# 8Bit-audio-7524-axelb.net
KiCad netlist of a schematic drawn in EAGLE
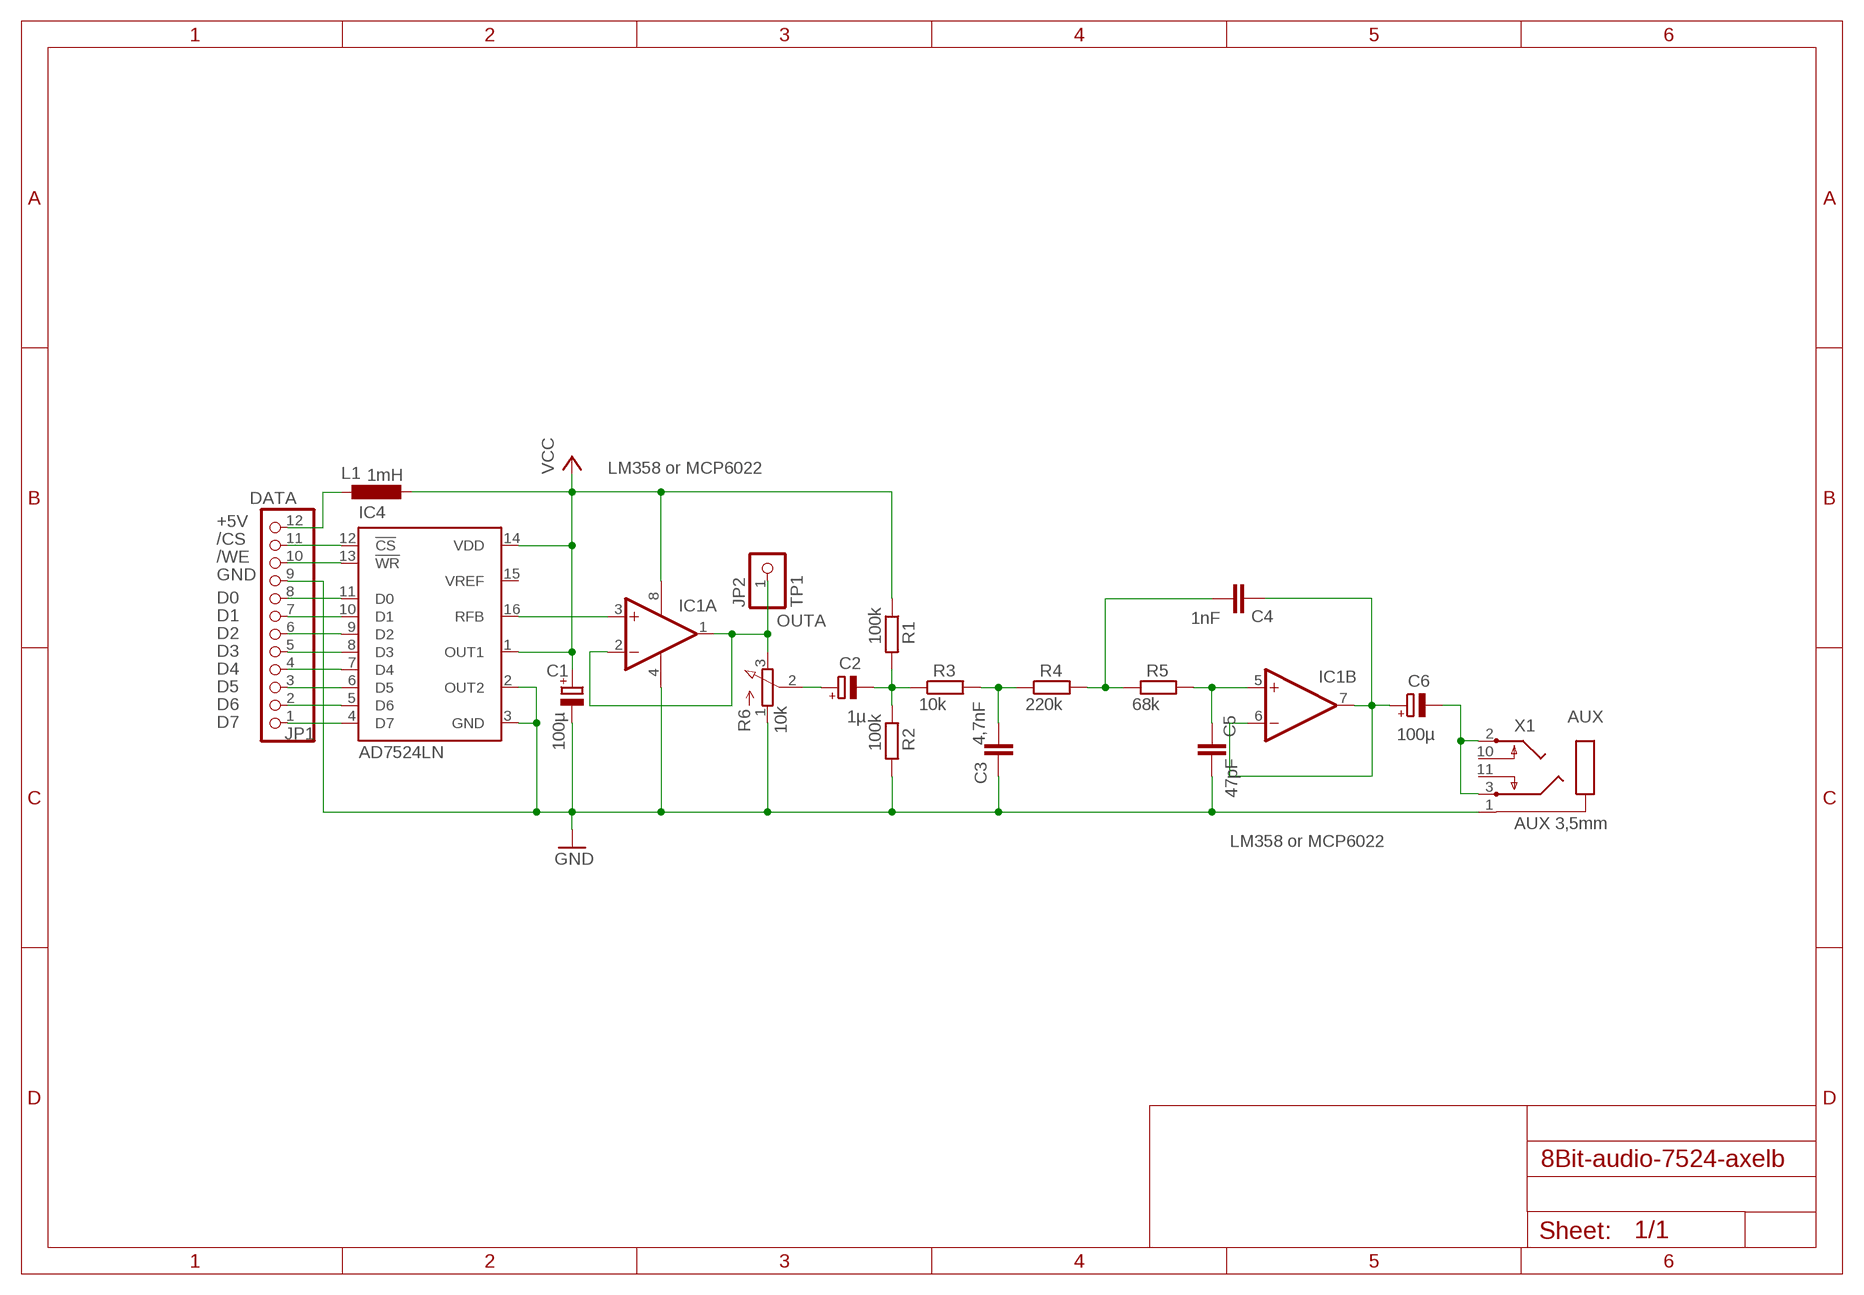
[diagram p0: schematic, sheet 1]

(export (version "E")
  (design (tool "Eeschema 10.0.6"))
  (components
    (comp (ref "C1")
      (value "100µ")
      (footprint "eagle-import:E5-5")
      (libsource (lib "eagle-import") (part "CPOL-EUE5-5"))
    )
    (comp (ref "C2")
      (value "1µ")
      (footprint "eagle-import:E5-5")
      (libsource (lib "eagle-import") (part "CPOL-EUE5-5"))
    )
    (comp (ref "C3")
      (value "4,7nF")
      (footprint "eagle-import:C075-032X103")
      (libsource (lib "eagle-import") (part "C-EU075-032X103"))
    )
    (comp (ref "C4")
      (value "1nF")
      (footprint "eagle-import:C075-032X103")
      (libsource (lib "eagle-import") (part "C-EU075-032X103"))
    )
    (comp (ref "C5")
      (value "47pF")
      (footprint "eagle-import:C075-032X103")
      (libsource (lib "eagle-import") (part "C-EU075-032X103"))
    )
    (comp (ref "C6")
      (value "100µ")
      (footprint "eagle-import:E5-5")
      (libsource (lib "eagle-import") (part "CPOL-EUE5-5"))
    )
    (comp (ref "IC1")
      (value "LM358 or MCP6022")
      (footprint "eagle-import:DIL08")
      (libsource (lib "eagle-import") (part "LM358N"))
    )
    (comp (ref "IC4")
      (value "AD7524LN")
      (footprint "eagle-import:DIL16")
      (fields (field (name "MF") "ALTERA CORPORATION") (field (name "MPN") "AD7524LNZ"))
      (libsource (lib "eagle-import") (part "AD7524NL"))
    )
    (comp (ref "JP1")
      (value "DATA")
      (footprint "eagle-import:1X12")
      (libsource (lib "eagle-import") (part "PINHD-1X12"))
    )
    (comp (ref "JP2")
      (value "TP1")
      (footprint "eagle-import:1X01")
      (libsource (lib "eagle-import") (part "PINHD-1X1"))
    )
    (comp (ref "L1")
      (value "1mH")
      (footprint "eagle-import:0207_10")
      (libsource (lib "eagle-import") (part "L-EU0207/10"))
    )
    (comp (ref "R1")
      (value "100k")
      (footprint "eagle-import:0207_10")
      (libsource (lib "eagle-import") (part "R-EU_0207/10"))
    )
    (comp (ref "R2")
      (value "100k")
      (footprint "eagle-import:0207_10")
      (libsource (lib "eagle-import") (part "R-EU_0207/10"))
    )
    (comp (ref "R3")
      (value "10k")
      (footprint "eagle-import:0207_10")
      (libsource (lib "eagle-import") (part "R-EU_0207/10"))
    )
    (comp (ref "R4")
      (value "220k")
      (footprint "eagle-import:0207_10")
      (libsource (lib "eagle-import") (part "R-EU_0207/10"))
    )
    (comp (ref "R5")
      (value "68k")
      (footprint "eagle-import:0207_10")
      (libsource (lib "eagle-import") (part "R-EU_0207/10"))
    )
    (comp (ref "R6")
      (value "10k")
      (footprint "eagle-import:3RP_1610N")
      (libsource (lib "eagle-import") (part "3RP/1610N"))
    )
    (comp (ref "X1")
      (value "AUX 3,5mm")
      (footprint "eagle-import:SJ1-352XN")
      (libsource (lib "eagle-import") (part "CON-SJ1-352XNSJ1-352XN"))
    )
  )
  (nets
    (net (code "1") (name "/+5V") (class "Default")
      (node (ref "JP1") (pin "12") (pinfunction "12_12") (pintype "passive"))
      (node (ref "L1") (pin "1") (pinfunction "1_1") (pintype "passive"))
    )
    (net (code "2") (name "/AUX") (class "Default")
      (node (ref "C6") (pin "-") (pinfunction "-_-") (pintype "passive"))
      (node (ref "X1") (pin "2") (pinfunction "2_2") (pintype "passive"))
      (node (ref "X1") (pin "3") (pinfunction "3_3") (pintype "passive"))
    )
    (net (code "3") (name "/D0") (class "Default")
      (node (ref "IC4") (pin "11") (pinfunction "D0_11") (pintype "input"))
      (node (ref "JP1") (pin "8") (pinfunction "8_8") (pintype "passive"))
    )
    (net (code "4") (name "/D1") (class "Default")
      (node (ref "IC4") (pin "10") (pinfunction "D1_10") (pintype "input"))
      (node (ref "JP1") (pin "7") (pinfunction "7_7") (pintype "passive"))
    )
    (net (code "5") (name "/D2") (class "Default")
      (node (ref "IC4") (pin "9") (pinfunction "D2_9") (pintype "input"))
      (node (ref "JP1") (pin "6") (pinfunction "6_6") (pintype "passive"))
    )
    (net (code "6") (name "/D3") (class "Default")
      (node (ref "IC4") (pin "8") (pinfunction "D3_8") (pintype "input"))
      (node (ref "JP1") (pin "5") (pinfunction "5_5") (pintype "passive"))
    )
    (net (code "7") (name "/D4") (class "Default")
      (node (ref "IC4") (pin "7") (pinfunction "D4_7") (pintype "input"))
      (node (ref "JP1") (pin "4") (pinfunction "4_4") (pintype "passive"))
    )
    (net (code "8") (name "/D5") (class "Default")
      (node (ref "IC4") (pin "6") (pinfunction "D5_6") (pintype "input"))
      (node (ref "JP1") (pin "3") (pinfunction "3_3") (pintype "passive"))
    )
    (net (code "9") (name "/D6") (class "Default")
      (node (ref "IC4") (pin "5") (pinfunction "D6_5") (pintype "input"))
      (node (ref "JP1") (pin "2") (pinfunction "2_2") (pintype "passive"))
    )
    (net (code "10") (name "/D7") (class "Default")
      (node (ref "IC4") (pin "4") (pinfunction "D7_4") (pintype "input"))
      (node (ref "JP1") (pin "1") (pinfunction "1_1") (pintype "passive"))
    )
    (net (code "11") (name "/OUTA") (class "Default")
      (node (ref "IC1") (pin "1") (pinfunction "OUT_1") (pintype "output"))
      (node (ref "IC1") (pin "2") (pinfunction "-IN_2") (pintype "input"))
      (node (ref "JP2") (pin "1") (pinfunction "1_1") (pintype "passive"))
      (node (ref "R6") (pin "3") (pinfunction "E_3") (pintype "passive"))
    )
    (net (code "12") (name "/{slash}CS") (class "Default")
      (node (ref "IC4") (pin "12") (pinfunction "~{CS}_12") (pintype "input"))
      (node (ref "JP1") (pin "11") (pinfunction "11_11") (pintype "passive"))
    )
    (net (code "13") (name "/{slash}WE") (class "Default")
      (node (ref "IC4") (pin "13") (pinfunction "~{WR}_13") (pintype "input"))
      (node (ref "JP1") (pin "10") (pinfunction "10_10") (pintype "passive"))
    )
    (net (code "14") (name "GND") (class "Default")
      (node (ref "C1") (pin "-") (pinfunction "-_-") (pintype "passive"))
      (node (ref "C3") (pin "1") (pinfunction "1_1") (pintype "passive"))
      (node (ref "C5") (pin "2") (pinfunction "2_2") (pintype "passive"))
      (node (ref "IC1") (pin "4") (pinfunction "V-_4") (pintype "power_in"))
      (node (ref "IC4") (pin "2") (pinfunction "OUT2_2") (pintype "passive"))
      (node (ref "IC4") (pin "3") (pinfunction "GND_3") (pintype "power_in"))
      (node (ref "JP1") (pin "9") (pinfunction "9_9") (pintype "passive"))
      (node (ref "R2") (pin "2") (pinfunction "2_2") (pintype "passive"))
      (node (ref "R6") (pin "1") (pinfunction "A_1") (pintype "passive"))
      (node (ref "X1") (pin "1") (pinfunction "1_1") (pintype "passive"))
    )
    (net (code "15") (name "Net-(C2-Pad-)") (class "Default")
      (node (ref "C2") (pin "-") (pinfunction "-_-") (pintype "passive"))
      (node (ref "R1") (pin "2") (pinfunction "2_2") (pintype "passive"))
      (node (ref "R2") (pin "1") (pinfunction "1_1") (pintype "passive"))
      (node (ref "R3") (pin "1") (pinfunction "1_1") (pintype "passive"))
    )
    (net (code "16") (name "Net-(C3-Pad2)") (class "Default")
      (node (ref "C3") (pin "2") (pinfunction "2_2") (pintype "passive"))
      (node (ref "R3") (pin "2") (pinfunction "2_2") (pintype "passive"))
      (node (ref "R4") (pin "1") (pinfunction "1_1") (pintype "passive"))
    )
    (net (code "17") (name "Net-(C4-Pad2)") (class "Default")
      (node (ref "C4") (pin "2") (pinfunction "2_2") (pintype "passive"))
      (node (ref "R4") (pin "2") (pinfunction "2_2") (pintype "passive"))
      (node (ref "R5") (pin "1") (pinfunction "1_1") (pintype "passive"))
    )
    (net (code "18") (name "Net-(IC1A-+IN)") (class "Default")
      (node (ref "IC1") (pin "3") (pinfunction "+IN_3") (pintype "input"))
      (node (ref "IC4") (pin "16") (pinfunction "RFB_16") (pintype "passive"))
    )
    (net (code "19") (name "Net-(IC1B-+IN)") (class "Default")
      (node (ref "C5") (pin "1") (pinfunction "1_1") (pintype "passive"))
      (node (ref "IC1") (pin "5") (pinfunction "+IN_5") (pintype "input"))
      (node (ref "R5") (pin "2") (pinfunction "2_2") (pintype "passive"))
    )
    (net (code "20") (name "Net-(IC1B--IN)") (class "Default")
      (node (ref "C4") (pin "1") (pinfunction "1_1") (pintype "passive"))
      (node (ref "C6") (pin "+") (pinfunction "+_+") (pintype "passive"))
      (node (ref "IC1") (pin "6") (pinfunction "-IN_6") (pintype "input"))
      (node (ref "IC1") (pin "7") (pinfunction "OUT_7") (pintype "output"))
    )
    (net (code "21") (name "Net-(R6-S)") (class "Default")
      (node (ref "C2") (pin "+") (pinfunction "+_+") (pintype "passive"))
      (node (ref "R6") (pin "2") (pinfunction "S_2") (pintype "passive"))
    )
    (net (code "22") (name "VCC") (class "Default")
      (node (ref "C1") (pin "+") (pinfunction "+_+") (pintype "passive"))
      (node (ref "IC1") (pin "8") (pinfunction "V+_8") (pintype "power_in"))
      (node (ref "IC4") (pin "1") (pinfunction "OUT1_1") (pintype "passive"))
      (node (ref "IC4") (pin "14") (pinfunction "VDD_14") (pintype "power_in"))
      (node (ref "L1") (pin "2") (pinfunction "2_2") (pintype "passive"))
      (node (ref "R1") (pin "1") (pinfunction "1_1") (pintype "passive"))
    )
    (net (code "23") (name "unconnected-(IC4-VREF-Pad15)") (class "Default")
      (node (ref "IC4") (pin "15") (pinfunction "VREF_15") (pintype "input"))
    )
    (net (code "24") (name "unconnected-(X1-Pad10)") (class "Default")
      (node (ref "X1") (pin "10") (pinfunction "10_10") (pintype "passive"))
    )
    (net (code "25") (name "unconnected-(X1-Pad11)") (class "Default")
      (node (ref "X1") (pin "11") (pinfunction "11_11") (pintype "passive"))
    )
  )
)
